# STM32.net
KiCad netlist of a schematic drawn in Altium Designer
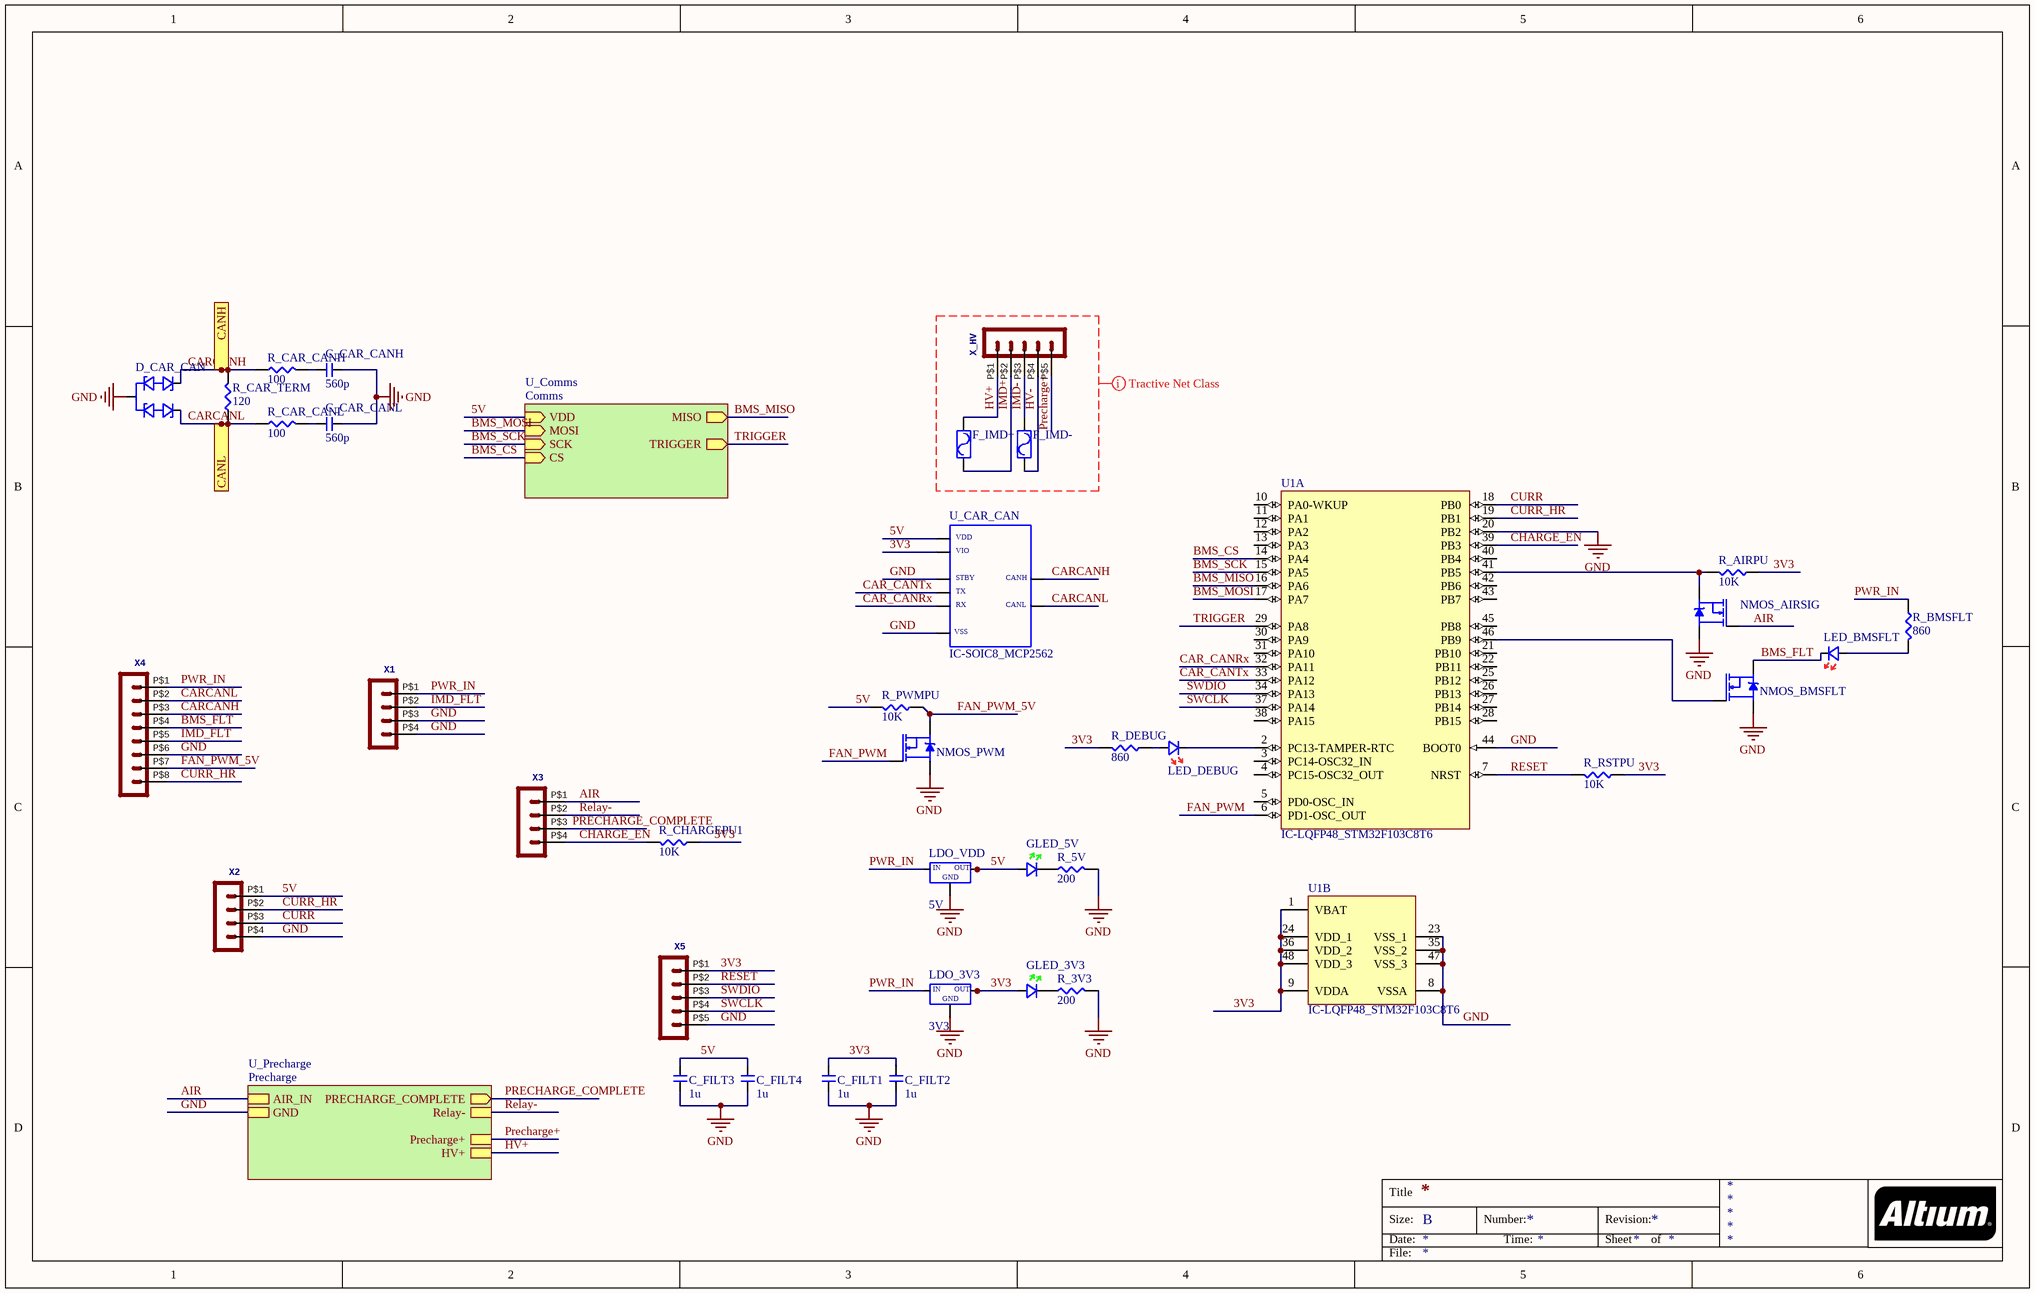
[diagram p0: STM32.SchDoc]

(export (version "E")
  (design (tool "Eeschema 10.0.6"))
  (components
    (comp (ref "C_CAR_CANH")
      (value "560p")
      (footprint "CAP-0603")
      (libsource (lib "altium-import") (part "root_0_CAP-0603_"))
    )
    (comp (ref "C_CAR_CANL")
      (value "560p")
      (footprint "CAP-0603")
      (libsource (lib "altium-import") (part "root_0_CAP-0603_"))
    )
    (comp (ref "C_FILT1")
      (value "1u")
      (footprint "CAP-0603")
      (libsource (lib "altium-import") (part "root_1_CAP-0603_"))
    )
    (comp (ref "C_FILT2")
      (value "1u")
      (footprint "CAP-0603")
      (libsource (lib "altium-import") (part "root_1_CAP-0603_"))
    )
    (comp (ref "C_FILT3")
      (value "1u")
      (footprint "CAP-0603")
      (libsource (lib "altium-import") (part "root_1_CAP-0603_"))
    )
    (comp (ref "C_FILT4")
      (value "1u")
      (footprint "CAP-0603")
      (libsource (lib "altium-import") (part "root_1_CAP-0603_"))
    )
    (comp (ref "D_CAR_CAN")
      (value "DIODE-SOT23_PESD1CAN")
      (footprint "SOT23")
      (libsource (lib "altium-import") (part "root_0_DIODE-SOT23_PESD1CAN_"))
    )
    (comp (ref "F_IMD+")
      (value "FUSE_885")
      (footprint "FUSE_885")
      (libsource (lib "ife19_Elec_Library") (part "FUSE_885"))
    )
    (comp (ref "F_IMD-")
      (value "FUSE_885")
      (footprint "FUSE_885")
      (libsource (lib "ife19_Elec_Library") (part "FUSE_885"))
    )
    (comp (ref "GLED_3V3")
      (value "~")
      (footprint "LEDGREEN-0603")
      (libsource (lib "altium-import") (part "root_0_LEDGREEN-0603_"))
    )
    (comp (ref "GLED_5V")
      (value "~")
      (footprint "LEDGREEN-0603")
      (libsource (lib "altium-import") (part "root_0_LEDGREEN-0603_"))
    )
    (comp (ref "LDO_3V3")
      (value "3V3")
      (footprint "SOT223")
      (libsource (lib "altium-import") (part "root_0_LDO-SOT223_SPX1117_"))
    )
    (comp (ref "LDO_VDD")
      (value "5V")
      (footprint "SOT223")
      (libsource (lib "altium-import") (part "root_0_LDO-SOT223_SPX1117_"))
    )
    (comp (ref "LED_BMSFLT")
      (value "LEDRED-0603")
      (footprint "LEDRED-0603")
      (libsource (lib "altium-import") (part "root_2_LEDRED-0603_"))
    )
    (comp (ref "LED_DEBUG")
      (value "LEDRED-0603")
      (footprint "LEDRED-0603")
      (libsource (lib "altium-import") (part "root_2_mirrored_LEDRED-0603_"))
    )
    (comp (ref "NMOS_AIRSIG")
      (value "NMOS-SOT23")
      (footprint "SOT23")
      (libsource (lib "altium-import") (part "root_0_NMOS-SOT23_"))
    )
    (comp (ref "NMOS_BMSFLT")
      (value "NMOS-SOT23")
      (footprint "SOT23")
      (libsource (lib "altium-import") (part "root_0_mirrored_NMOS-SOT23_"))
    )
    (comp (ref "NMOS_PWM")
      (value "NMOS-SOT23")
      (footprint "SOT23")
      (libsource (lib "altium-import") (part "root_0_mirrored_NMOS-SOT23_"))
    )
    (comp (ref "R_3V3")
      (value "200")
      (footprint "RES-0603")
      (libsource (lib "altium-import") (part "root_0_RES-0603_"))
    )
    (comp (ref "R_5V")
      (value "200")
      (footprint "RES-0603")
      (libsource (lib "altium-import") (part "root_0_RES-0603_"))
    )
    (comp (ref "R_AIRPU")
      (value "10K")
      (footprint "RES-0603")
      (libsource (lib "altium-import") (part "root_2_RES-0603_"))
    )
    (comp (ref "R_BMSFLT")
      (value "860")
      (footprint "RES-0603")
      (libsource (lib "altium-import") (part "root_1_mirrored_RES-0603_"))
    )
    (comp (ref "R_CAR_CANH")
      (value "100")
      (footprint "RES-0603")
      (libsource (lib "altium-import") (part "root_0_RES-0603_"))
    )
    (comp (ref "R_CAR_CANL")
      (value "100")
      (footprint "RES-0603")
      (libsource (lib "altium-import") (part "root_0_RES-0603_"))
    )
    (comp (ref "R_CAR_TERM")
      (value "120")
      (footprint "RES-0603")
      (libsource (lib "altium-import") (part "root_1_RES-0603_"))
    )
    (comp (ref "R_CHARGEPU1")
      (value "10K")
      (footprint "RES-0603")
      (libsource (lib "altium-import") (part "root_2_RES-0603_"))
    )
    (comp (ref "R_DEBUG")
      (value "860")
      (footprint "RES-0603")
      (libsource (lib "altium-import") (part "root_2_RES-0603_"))
    )
    (comp (ref "R_PWMPU")
      (value "10K")
      (footprint "RES-0603")
      (libsource (lib "altium-import") (part "root_2_mirrored_RES-0603_"))
    )
    (comp (ref "R_RSTPU")
      (value "10K")
      (footprint "RES-0603")
      (libsource (lib "altium-import") (part "root_2_RES-0603_"))
    )
    (comp (ref "U1")
      (value "IC-LQFP48_STM32F103C8T6")
      (footprint "STM-LQFP48_M")
      (fields (field (name "PARTNUMBER") "STM32F103C8T6"))
      (libsource (lib "ife19_Elec_Library") (part "IC-LQFP48_STM32F103C8T6"))
    )
    (comp (ref "U_CAR_CAN")
      (value "IC-SOIC8_MCP2562")
      (footprint "SOIC8")
      (libsource (lib "altium-import") (part "root_0_IC-SOIC8_MCP2562_"))
    )
    (comp (ref "X1")
      (value "Molex - Micro-Fit 3.0 Series connector,  3.00mm (0.118\") pitch header, 4 positions.")
      (footprint "43650-0424")
      (libsource (lib "ife19_Elec_Conn_Library") (part "POS4_MF43650-0424"))
    )
    (comp (ref "X2")
      (value "Molex - Micro-Fit 3.0 Series connector,  3.00mm (0.118\") pitch header, 4 positions.")
      (footprint "43650-0424")
      (libsource (lib "ife19_Elec_Conn_Library") (part "POS4_MF43650-0424"))
    )
    (comp (ref "X3")
      (value "Molex - Micro-Fit 3.0 Series connector,  3.00mm (0.118\") pitch header, 4 positions.")
      (footprint "43650-0424")
      (libsource (lib "ife19_Elec_Conn_Library") (part "POS4_MF43650-0424"))
    )
    (comp (ref "X4")
      (value "Molex - Micro-Fit 3.0 Series connector,  3.00mm (0.118\") pitch header, 8 positions.")
      (footprint "43650-0824")
      (libsource (lib "MOLEX Micro-Fit") (part "HEADER_POS8_?43650-0824"))
    )
    (comp (ref "X5")
      (value "~")
      (footprint "POS5_254MM_MALE")
      (libsource (lib "altium-import") (part "root_0_mirrored_POS5_254MM_MALE_"))
    )
    (comp (ref "X_HV")
      (value "Molex - Micro-Fit 3.0 Series connector,  3.00mm (0.118\") pitch header, 5 positions.")
      (footprint "43650-0524")
      (libsource (lib "ife19_Elec_Conn_Library") (part "POS5_MF43650-0524"))
    )
  )
  (nets
    (net (code "1") (name "/3V3") (class "Default")
      (node (ref "C_FILT1") (pin "2") (pinfunction "2_2") (pintype "passive"))
      (node (ref "C_FILT2") (pin "2") (pinfunction "2_2") (pintype "passive"))
      (node (ref "GLED_3V3") (pin "A") (pinfunction "A_A") (pintype "passive"))
      (node (ref "LDO_3V3") (pin "2") (pinfunction "2_2") (pintype "passive"))
      (node (ref "LDO_3V3") (pin "4") (pinfunction "4_4") (pintype "passive"))
      (node (ref "R_AIRPU") (pin "1") (pinfunction "1_1") (pintype "passive"))
      (node (ref "R_CHARGEPU1") (pin "1") (pinfunction "1_1") (pintype "passive"))
      (node (ref "R_DEBUG") (pin "2") (pinfunction "2_2") (pintype "passive"))
      (node (ref "R_RSTPU") (pin "1") (pinfunction "1_1") (pintype "passive"))
      (node (ref "U1") (pin "1") (pinfunction "VBAT_1") (pintype "power_in"))
      (node (ref "U1") (pin "24") (pinfunction "VDD_1_24") (pintype "power_in"))
      (node (ref "U1") (pin "36") (pinfunction "VDD_2_36") (pintype "power_in"))
      (node (ref "U1") (pin "48") (pinfunction "VDD_3_48") (pintype "power_in"))
      (node (ref "U1") (pin "9") (pinfunction "VDDA_9") (pintype "power_in"))
      (node (ref "U_CAR_CAN") (pin "5") (pinfunction "5_5") (pintype "passive"))
      (node (ref "X5") (pin "P$1") (pinfunction "1_P$1") (pintype "passive"))
    )
    (net (code "2") (name "/5V") (class "Default")
      (node (ref "C_FILT3") (pin "2") (pinfunction "2_2") (pintype "passive"))
      (node (ref "C_FILT4") (pin "2") (pinfunction "2_2") (pintype "passive"))
      (node (ref "GLED_5V") (pin "A") (pinfunction "A_A") (pintype "passive"))
      (node (ref "LDO_VDD") (pin "2") (pinfunction "2_2") (pintype "passive"))
      (node (ref "LDO_VDD") (pin "4") (pinfunction "4_4") (pintype "passive"))
      (node (ref "R_PWMPU") (pin "1") (pinfunction "1_1") (pintype "passive"))
      (node (ref "U_CAR_CAN") (pin "3") (pinfunction "3_3") (pintype "passive"))
      (node (ref "X2") (pin "P$1") (pinfunction "1_P$1") (pintype "passive"))
    )
    (net (code "3") (name "/AIR") (class "Default")
      (node (ref "NMOS_AIRSIG") (pin "1") (pinfunction "G_1") (pintype "passive"))
      (node (ref "X3") (pin "P$1") (pinfunction "1_P$1") (pintype "passive"))
    )
    (net (code "4") (name "/BMS_CS") (class "Default")
      (node (ref "U1") (pin "14") (pinfunction "PA4_14") (pintype "bidirectional"))
    )
    (net (code "5") (name "/BMS_FLT") (class "Default")
      (node (ref "LED_BMSFLT") (pin "K") (pinfunction "K_K") (pintype "passive"))
      (node (ref "NMOS_BMSFLT") (pin "3") (pinfunction "D_3") (pintype "passive"))
      (node (ref "X4") (pin "P$4") (pinfunction "4_P$4") (pintype "passive"))
    )
    (net (code "6") (name "/BMS_MISO") (class "Default")
      (node (ref "U1") (pin "16") (pinfunction "PA6_16") (pintype "bidirectional"))
    )
    (net (code "7") (name "/BMS_MOSI") (class "Default")
      (node (ref "U1") (pin "17") (pinfunction "PA7_17") (pintype "bidirectional"))
    )
    (net (code "8") (name "/BMS_SCK") (class "Default")
      (node (ref "U1") (pin "15") (pinfunction "PA5_15") (pintype "bidirectional"))
    )
    (net (code "9") (name "/CARCANH") (class "Default")
      (node (ref "D_CAR_CAN") (pin "2") (pinfunction "CAN2_2") (pintype "passive"))
      (node (ref "R_CAR_CANH") (pin "1") (pinfunction "1_1") (pintype "passive"))
      (node (ref "R_CAR_TERM") (pin "2") (pinfunction "2_2") (pintype "passive"))
      (node (ref "U_CAR_CAN") (pin "7") (pinfunction "7_7") (pintype "passive"))
      (node (ref "X4") (pin "P$3") (pinfunction "3_P$3") (pintype "passive"))
    )
    (net (code "10") (name "/CARCANL") (class "Default")
      (node (ref "D_CAR_CAN") (pin "1") (pinfunction "CAN1_1") (pintype "passive"))
      (node (ref "R_CAR_CANL") (pin "1") (pinfunction "1_1") (pintype "passive"))
      (node (ref "R_CAR_TERM") (pin "1") (pinfunction "1_1") (pintype "passive"))
      (node (ref "U_CAR_CAN") (pin "6") (pinfunction "6_6") (pintype "passive"))
      (node (ref "X4") (pin "P$2") (pinfunction "2_P$2") (pintype "passive"))
    )
    (net (code "11") (name "/CAR_CANRx") (class "Default")
      (node (ref "U1") (pin "32") (pinfunction "PA11_32") (pintype "bidirectional"))
      (node (ref "U_CAR_CAN") (pin "4") (pinfunction "4_4") (pintype "passive"))
    )
    (net (code "12") (name "/CAR_CANTx") (class "Default")
      (node (ref "U1") (pin "33") (pinfunction "PA12_33") (pintype "bidirectional"))
      (node (ref "U_CAR_CAN") (pin "1") (pinfunction "1_1") (pintype "passive"))
    )
    (net (code "13") (name "/CHARGE_EN") (class "Default")
      (node (ref "R_CHARGEPU1") (pin "2") (pinfunction "2_2") (pintype "passive"))
      (node (ref "U1") (pin "39") (pinfunction "PB3_39") (pintype "bidirectional"))
      (node (ref "X3") (pin "P$4") (pinfunction "4_P$4") (pintype "passive"))
    )
    (net (code "14") (name "/CURR") (class "Default")
      (node (ref "U1") (pin "18") (pinfunction "PB0_18") (pintype "bidirectional"))
      (node (ref "X2") (pin "P$3") (pinfunction "3_P$3") (pintype "passive"))
    )
    (net (code "15") (name "/CURR_HR") (class "Default")
      (node (ref "U1") (pin "19") (pinfunction "PB1_19") (pintype "bidirectional"))
      (node (ref "X2") (pin "P$2") (pinfunction "2_P$2") (pintype "passive"))
      (node (ref "X4") (pin "P$8") (pinfunction "8_P$8") (pintype "passive"))
    )
    (net (code "16") (name "/FAN_PWM") (class "Default")
      (node (ref "NMOS_PWM") (pin "1") (pinfunction "G_1") (pintype "passive"))
      (node (ref "U1") (pin "6") (pinfunction "PD1-OSC_OUT_6") (pintype "bidirectional"))
    )
    (net (code "17") (name "/FAN_PWM_5V") (class "Default")
      (node (ref "NMOS_PWM") (pin "3") (pinfunction "D_3") (pintype "passive"))
      (node (ref "R_PWMPU") (pin "2") (pinfunction "2_2") (pintype "passive"))
      (node (ref "X4") (pin "P$7") (pinfunction "7_P$7") (pintype "passive"))
    )
    (net (code "18") (name "/HV+") (class "Default")
      (node (ref "F_IMD+") (pin "1") (pinfunction "1_1") (pintype "passive"))
      (node (ref "X_HV") (pin "P$1") (pinfunction "1_P$1") (pintype "passive"))
    )
    (net (code "19") (name "/HV-") (class "Default")
      (node (ref "F_IMD-") (pin "2") (pinfunction "2_2") (pintype "passive"))
      (node (ref "X_HV") (pin "P$4") (pinfunction "4_P$4") (pintype "passive"))
    )
    (net (code "20") (name "/IMD+") (class "Default")
      (node (ref "F_IMD+") (pin "2") (pinfunction "2_2") (pintype "passive"))
      (node (ref "X_HV") (pin "P$2") (pinfunction "2_P$2") (pintype "passive"))
    )
    (net (code "21") (name "/IMD-") (class "Default")
      (node (ref "F_IMD-") (pin "1") (pinfunction "1_1") (pintype "passive"))
      (node (ref "X_HV") (pin "P$3") (pinfunction "3_P$3") (pintype "passive"))
    )
    (net (code "22") (name "/IMD_FLT") (class "Default")
      (node (ref "X1") (pin "P$2") (pinfunction "2_P$2") (pintype "passive"))
      (node (ref "X4") (pin "P$5") (pinfunction "5_P$5") (pintype "passive"))
    )
    (net (code "23") (name "/PRECHARGE_COMPLETE") (class "Default")
      (node (ref "X3") (pin "P$3") (pinfunction "3_P$3") (pintype "passive"))
    )
    (net (code "24") (name "/PWR_IN") (class "Default")
      (node (ref "LDO_3V3") (pin "3") (pinfunction "3_3") (pintype "passive"))
      (node (ref "LDO_VDD") (pin "3") (pinfunction "3_3") (pintype "passive"))
      (node (ref "R_BMSFLT") (pin "2") (pinfunction "2_2") (pintype "passive"))
      (node (ref "X1") (pin "P$1") (pinfunction "1_P$1") (pintype "passive"))
      (node (ref "X4") (pin "P$1") (pinfunction "1_P$1") (pintype "passive"))
    )
    (net (code "25") (name "/Precharge+") (class "Default")
      (node (ref "X_HV") (pin "P$5") (pinfunction "5_P$5") (pintype "passive"))
    )
    (net (code "26") (name "/RESET") (class "Default")
      (node (ref "R_RSTPU") (pin "2") (pinfunction "2_2") (pintype "passive"))
      (node (ref "U1") (pin "7") (pinfunction "NRST_7") (pintype "bidirectional"))
      (node (ref "X5") (pin "P$2") (pinfunction "2_P$2") (pintype "passive"))
    )
    (net (code "27") (name "/Relay-") (class "Default")
      (node (ref "X3") (pin "P$2") (pinfunction "2_P$2") (pintype "passive"))
    )
    (net (code "28") (name "/SWCLK") (class "Default")
      (node (ref "U1") (pin "37") (pinfunction "PA14_37") (pintype "bidirectional"))
      (node (ref "X5") (pin "P$4") (pinfunction "4_P$4") (pintype "passive"))
    )
    (net (code "29") (name "/SWDIO") (class "Default")
      (node (ref "U1") (pin "34") (pinfunction "PA13_34") (pintype "bidirectional"))
      (node (ref "X5") (pin "P$3") (pinfunction "3_P$3") (pintype "passive"))
    )
    (net (code "30") (name "/TRIGGER") (class "Default")
      (node (ref "U1") (pin "29") (pinfunction "PA8_29") (pintype "bidirectional"))
    )
    (net (code "31") (name "GND") (class "Default")
      (node (ref "C_CAR_CANH") (pin "2") (pinfunction "2_2") (pintype "passive"))
      (node (ref "C_CAR_CANL") (pin "2") (pinfunction "2_2") (pintype "passive"))
      (node (ref "C_FILT1") (pin "1") (pinfunction "1_1") (pintype "passive"))
      (node (ref "C_FILT2") (pin "1") (pinfunction "1_1") (pintype "passive"))
      (node (ref "C_FILT3") (pin "1") (pinfunction "1_1") (pintype "passive"))
      (node (ref "C_FILT4") (pin "1") (pinfunction "1_1") (pintype "passive"))
      (node (ref "D_CAR_CAN") (pin "3") (pinfunction "G_3") (pintype "passive"))
      (node (ref "LDO_3V3") (pin "1") (pinfunction "1_1") (pintype "passive"))
      (node (ref "LDO_VDD") (pin "1") (pinfunction "1_1") (pintype "passive"))
      (node (ref "NMOS_AIRSIG") (pin "2") (pinfunction "S_2") (pintype "passive"))
      (node (ref "NMOS_BMSFLT") (pin "2") (pinfunction "S_2") (pintype "passive"))
      (node (ref "NMOS_PWM") (pin "2") (pinfunction "S_2") (pintype "passive"))
      (node (ref "R_3V3") (pin "2") (pinfunction "2_2") (pintype "passive"))
      (node (ref "R_5V") (pin "2") (pinfunction "2_2") (pintype "passive"))
      (node (ref "U1") (pin "20") (pinfunction "PB2_20") (pintype "bidirectional"))
      (node (ref "U1") (pin "23") (pinfunction "VSS_1_23") (pintype "power_in"))
      (node (ref "U1") (pin "35") (pinfunction "VSS_2_35") (pintype "power_in"))
      (node (ref "U1") (pin "44") (pinfunction "BOOT0_44") (pintype "input"))
      (node (ref "U1") (pin "47") (pinfunction "VSS_3_47") (pintype "power_in"))
      (node (ref "U1") (pin "8") (pinfunction "VSSA_8") (pintype "power_in"))
      (node (ref "U_CAR_CAN") (pin "2") (pinfunction "2_2") (pintype "passive"))
      (node (ref "U_CAR_CAN") (pin "8") (pinfunction "8_8") (pintype "passive"))
      (node (ref "X1") (pin "P$3") (pinfunction "3_P$3") (pintype "passive"))
      (node (ref "X1") (pin "P$4") (pinfunction "4_P$4") (pintype "passive"))
      (node (ref "X2") (pin "P$4") (pinfunction "4_P$4") (pintype "passive"))
      (node (ref "X4") (pin "P$6") (pinfunction "6_P$6") (pintype "passive"))
      (node (ref "X5") (pin "P$5") (pinfunction "5_P$5") (pintype "passive"))
    )
    (net (code "32") (name "Net-(C_CAR_CANH-Pad1)") (class "Default")
      (node (ref "C_CAR_CANH") (pin "1") (pinfunction "1_1") (pintype "passive"))
      (node (ref "R_CAR_CANH") (pin "2") (pinfunction "2_2") (pintype "passive"))
    )
    (net (code "33") (name "Net-(C_CAR_CANL-Pad1)") (class "Default")
      (node (ref "C_CAR_CANL") (pin "1") (pinfunction "1_1") (pintype "passive"))
      (node (ref "R_CAR_CANL") (pin "2") (pinfunction "2_2") (pintype "passive"))
    )
    (net (code "34") (name "Net-(GLED_3V3-PadK)") (class "Default")
      (node (ref "GLED_3V3") (pin "K") (pinfunction "K_K") (pintype "passive"))
      (node (ref "R_3V3") (pin "1") (pinfunction "1_1") (pintype "passive"))
    )
    (net (code "35") (name "Net-(GLED_5V-PadK)") (class "Default")
      (node (ref "GLED_5V") (pin "K") (pinfunction "K_K") (pintype "passive"))
      (node (ref "R_5V") (pin "1") (pinfunction "1_1") (pintype "passive"))
    )
    (net (code "36") (name "Net-(LED_BMSFLT-PadA)") (class "Default")
      (node (ref "LED_BMSFLT") (pin "A") (pinfunction "A_A") (pintype "passive"))
      (node (ref "R_BMSFLT") (pin "1") (pinfunction "1_1") (pintype "passive"))
    )
    (net (code "37") (name "Net-(LED_DEBUG-PadA)") (class "Default")
      (node (ref "LED_DEBUG") (pin "A") (pinfunction "A_A") (pintype "passive"))
      (node (ref "R_DEBUG") (pin "1") (pinfunction "1_1") (pintype "passive"))
    )
    (net (code "38") (name "Net-(NMOS_AIRSIG-D)") (class "Default")
      (node (ref "NMOS_AIRSIG") (pin "3") (pinfunction "D_3") (pintype "passive"))
      (node (ref "R_AIRPU") (pin "2") (pinfunction "2_2") (pintype "passive"))
      (node (ref "U1") (pin "41") (pinfunction "PB5_41") (pintype "bidirectional"))
    )
    (net (code "39") (name "Net-(NMOS_BMSFLT-G)") (class "Default")
      (node (ref "NMOS_BMSFLT") (pin "1") (pinfunction "G_1") (pintype "passive"))
      (node (ref "U1") (pin "46") (pinfunction "PB9_46") (pintype "bidirectional"))
    )
    (net (code "40") (name "Net-(U1A-PC13-TAMPER-RTC)") (class "Default")
      (node (ref "LED_DEBUG") (pin "K") (pinfunction "K_K") (pintype "passive"))
      (node (ref "U1") (pin "2") (pinfunction "PC13-TAMPER-RTC_2") (pintype "bidirectional"))
    )
    (net (code "41") (name "unconnected-(U1A-PA0-WKUP-Pad10)") (class "Default")
      (node (ref "U1") (pin "10") (pinfunction "PA0-WKUP_10") (pintype "bidirectional"))
    )
    (net (code "42") (name "unconnected-(U1A-PA1-Pad11)") (class "Default")
      (node (ref "U1") (pin "11") (pinfunction "PA1_11") (pintype "bidirectional"))
    )
    (net (code "43") (name "unconnected-(U1A-PA2-Pad12)") (class "Default")
      (node (ref "U1") (pin "12") (pinfunction "PA2_12") (pintype "bidirectional"))
    )
    (net (code "44") (name "unconnected-(U1A-PA3-Pad13)") (class "Default")
      (node (ref "U1") (pin "13") (pinfunction "PA3_13") (pintype "bidirectional"))
    )
    (net (code "45") (name "unconnected-(U1A-PA9-Pad30)") (class "Default")
      (node (ref "U1") (pin "30") (pinfunction "PA9_30") (pintype "bidirectional"))
    )
    (net (code "46") (name "unconnected-(U1A-PA10-Pad31)") (class "Default")
      (node (ref "U1") (pin "31") (pinfunction "PA10_31") (pintype "bidirectional"))
    )
    (net (code "47") (name "unconnected-(U1A-PA15-Pad38)") (class "Default")
      (node (ref "U1") (pin "38") (pinfunction "PA15_38") (pintype "bidirectional"))
    )
    (net (code "48") (name "unconnected-(U1A-PB4-Pad40)") (class "Default")
      (node (ref "U1") (pin "40") (pinfunction "PB4_40") (pintype "bidirectional"))
    )
    (net (code "49") (name "unconnected-(U1A-PB6-Pad42)") (class "Default")
      (node (ref "U1") (pin "42") (pinfunction "PB6_42") (pintype "bidirectional"))
    )
    (net (code "50") (name "unconnected-(U1A-PB7-Pad43)") (class "Default")
      (node (ref "U1") (pin "43") (pinfunction "PB7_43") (pintype "bidirectional"))
    )
    (net (code "51") (name "unconnected-(U1A-PB8-Pad45)") (class "Default")
      (node (ref "U1") (pin "45") (pinfunction "PB8_45") (pintype "bidirectional"))
    )
    (net (code "52") (name "unconnected-(U1A-PB10-Pad21)") (class "Default")
      (node (ref "U1") (pin "21") (pinfunction "PB10_21") (pintype "bidirectional"))
    )
    (net (code "53") (name "unconnected-(U1A-PB11-Pad22)") (class "Default")
      (node (ref "U1") (pin "22") (pinfunction "PB11_22") (pintype "bidirectional"))
    )
    (net (code "54") (name "unconnected-(U1A-PB12-Pad25)") (class "Default")
      (node (ref "U1") (pin "25") (pinfunction "PB12_25") (pintype "bidirectional"))
    )
    (net (code "55") (name "unconnected-(U1A-PB13-Pad26)") (class "Default")
      (node (ref "U1") (pin "26") (pinfunction "PB13_26") (pintype "bidirectional"))
    )
    (net (code "56") (name "unconnected-(U1A-PB14-Pad27)") (class "Default")
      (node (ref "U1") (pin "27") (pinfunction "PB14_27") (pintype "bidirectional"))
    )
    (net (code "57") (name "unconnected-(U1A-PB15-Pad28)") (class "Default")
      (node (ref "U1") (pin "28") (pinfunction "PB15_28") (pintype "bidirectional"))
    )
    (net (code "58") (name "unconnected-(U1A-PC14-OSC32_IN-Pad3)") (class "Default")
      (node (ref "U1") (pin "3") (pinfunction "PC14-OSC32_IN_3") (pintype "bidirectional"))
    )
    (net (code "59") (name "unconnected-(U1A-PC15-OSC32_OUT-Pad4)") (class "Default")
      (node (ref "U1") (pin "4") (pinfunction "PC15-OSC32_OUT_4") (pintype "bidirectional"))
    )
    (net (code "60") (name "unconnected-(U1A-PD0-OSC_IN-Pad5)") (class "Default")
      (node (ref "U1") (pin "5") (pinfunction "PD0-OSC_IN_5") (pintype "bidirectional"))
    )
  )
)
